# inductance_meter.net
KiCad netlist of a schematic drawn in EAGLE
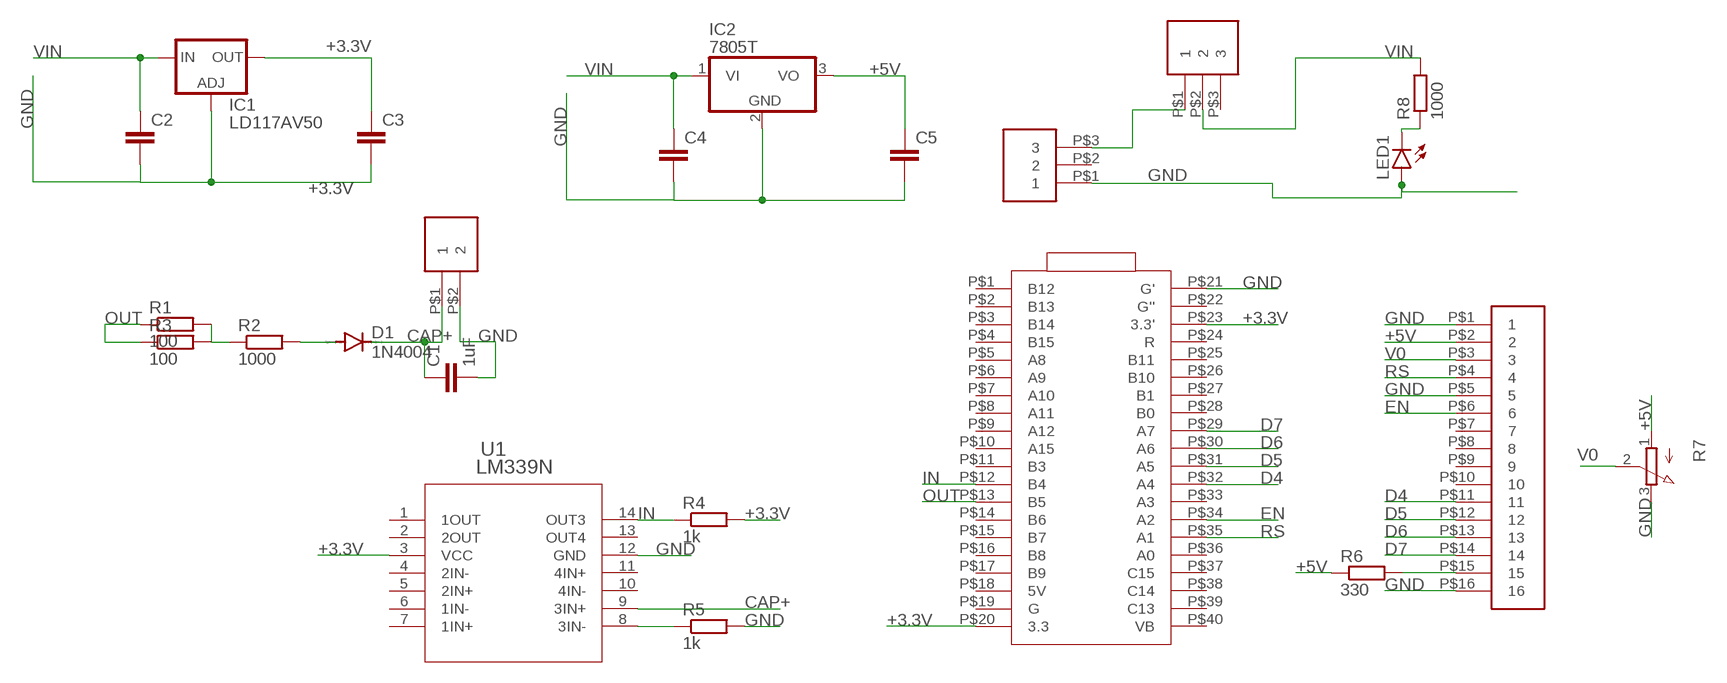
[diagram p0: schematic, sheet 1]

(export (version "E")
  (design (tool "Eeschema 10.0.6"))
  (components
    (comp (ref "C1")
      (value "1uF")
      (footprint "eagle-import:C050-075X075")
      (libsource (lib "eagle-import") (part "C-EU050-075X075"))
    )
    (comp (ref "C2")
      (value "C-EU025-030X050")
      (footprint "eagle-import:C025-030X050")
      (libsource (lib "eagle-import") (part "C-EU025-030X050"))
    )
    (comp (ref "C3")
      (value "C-EU025-030X050")
      (footprint "eagle-import:C025-030X050")
      (libsource (lib "eagle-import") (part "C-EU025-030X050"))
    )
    (comp (ref "C4")
      (value "C-EU025-030X050")
      (footprint "eagle-import:C025-030X050")
      (libsource (lib "eagle-import") (part "C-EU025-030X050"))
    )
    (comp (ref "C5")
      (value "C-EU025-030X050")
      (footprint "eagle-import:C025-030X050")
      (libsource (lib "eagle-import") (part "C-EU025-030X050"))
    )
    (comp (ref "D1")
      (value "1N4004")
      (footprint "eagle-import:DO41-10")
      (libsource (lib "eagle-import") (part "1N4004"))
    )
    (comp (ref "IC1")
      (value "LD117AV50")
      (footprint "eagle-import:TO220L1")
      (libsource (lib "eagle-import") (part "LD117A?V50"))
    )
    (comp (ref "IC2")
      (value "7805T")
      (footprint "eagle-import:TO220H")
      (libsource (lib "eagle-import") (part "78T05"))
    )
    (comp (ref "LED1")
      (value "TLLR4400")
      (footprint "eagle-import:LED3MM")
      (fields (field (name "MF") "VISHAY SEMICONDUCTOR"))
      (libsource (lib "eagle-import") (part "TLLR4400"))
    )
    (comp (ref "R1")
      (value "100")
      (footprint "eagle-import:P0817_22")
      (libsource (lib "eagle-import") (part "R-EU_0817/22"))
    )
    (comp (ref "R2")
      (value "1000")
      (footprint "eagle-import:P0817_22")
      (libsource (lib "eagle-import") (part "R-EU_0817/22"))
    )
    (comp (ref "R3")
      (value "100")
      (footprint "eagle-import:P0817_22")
      (libsource (lib "eagle-import") (part "R-EU_0817/22"))
    )
    (comp (ref "R4")
      (value "1k")
      (footprint "eagle-import:P0817_22")
      (libsource (lib "eagle-import") (part "R-EU_0817/22"))
    )
    (comp (ref "R5")
      (value "1k")
      (footprint "eagle-import:P0817_22")
      (libsource (lib "eagle-import") (part "R-EU_0817/22"))
    )
    (comp (ref "R6")
      (value "330")
      (footprint "eagle-import:0617_17")
      (libsource (lib "eagle-import") (part "R-EU_0617/17"))
    )
    (comp (ref "R7")
      (value "3RP/1610N")
      (footprint "eagle-import:3RP_1610N")
      (libsource (lib "eagle-import") (part "3RP/1610N"))
    )
    (comp (ref "R8")
      (value "1000")
      (footprint "eagle-import:P0817_22")
      (libsource (lib "eagle-import") (part "R-EU_0817/22"))
    )
    (comp (ref "U$2")
      (value "HEADER_16")
      (footprint "eagle-import:HEADER_16_FOOT")
      (libsource (lib "eagle-import") (part "HEADER_16"))
    )
    (comp (ref "U$3")
      (value "BLUE_PILL_EA")
      (footprint "eagle-import:BLUE_PILL_FOOT")
      (libsource (lib "eagle-import") (part "BLUE_PILL_EA"))
    )
    (comp (ref "U$5")
      (value "HEADER_2")
      (footprint "eagle-import:HEADER_2_FOOT")
      (libsource (lib "eagle-import") (part "HEADER_2"))
    )
    (comp (ref "U$7")
      (value "HEADER_3")
      (footprint "eagle-import:HEADER_3_FOOT")
      (libsource (lib "eagle-import") (part "HEADER_3"))
    )
    (comp (ref "U$9")
      (value "HEADER_3")
      (footprint "eagle-import:HEADER_3_FOOT")
      (libsource (lib "eagle-import") (part "HEADER_3"))
    )
    (comp (ref "U1")
      (value "LM339N")
      (footprint "eagle-import:PDIP14_6P60X19P69_ONS")
      (fields (field (name "COPYRIGHT") "Copyright (C) 2018 Accelerated Designs. All rights reserved"))
      (libsource (lib "eagle-import") (part "LM339N"))
    )
  )
  (nets
    (net (code "1") (name "/+3.3V") (class "Default")
      (node (ref "C3") (pin "1") (pinfunction "1_1") (pintype "passive"))
      (node (ref "IC1") (pin "2") (pinfunction "OUT_2") (pintype "passive"))
      (node (ref "R4") (pin "2") (pinfunction "2_2") (pintype "passive"))
      (node (ref "U$3") (pin "P$20") (pinfunction "3.3_P$20") (pintype "bidirectional"))
      (node (ref "U$3") (pin "P$23") (pinfunction "3.3'_P$23") (pintype "bidirectional"))
      (node (ref "U1") (pin "3") (pinfunction "VCC_3") (pintype "power_in"))
    )
    (net (code "2") (name "/+5V") (class "Default")
      (node (ref "C5") (pin "1") (pinfunction "1_1") (pintype "passive"))
      (node (ref "IC2") (pin "3") (pinfunction "VO_3") (pintype "passive"))
      (node (ref "R6") (pin "1") (pinfunction "1_1") (pintype "passive"))
      (node (ref "R7") (pin "1") (pinfunction "A_1") (pintype "passive"))
      (node (ref "U$2") (pin "P$2") (pinfunction "2_P$2") (pintype "bidirectional"))
    )
    (net (code "3") (name "/CAP+") (class "Default")
      (node (ref "C1") (pin "1") (pinfunction "1_1") (pintype "passive"))
      (node (ref "D1") (pin "C") (pinfunction "C_C") (pintype "passive"))
      (node (ref "U$5") (pin "P$1") (pinfunction "1_P$1") (pintype "bidirectional"))
      (node (ref "U1") (pin "9") (pinfunction "3IN+_9") (pintype "input"))
    )
    (net (code "4") (name "/D4") (class "Default")
      (node (ref "U$2") (pin "P$11") (pinfunction "11_P$11") (pintype "bidirectional"))
      (node (ref "U$3") (pin "P$32") (pinfunction "A4_P$32") (pintype "bidirectional"))
    )
    (net (code "5") (name "/D5") (class "Default")
      (node (ref "U$2") (pin "P$12") (pinfunction "12_P$12") (pintype "bidirectional"))
      (node (ref "U$3") (pin "P$31") (pinfunction "A5_P$31") (pintype "bidirectional"))
    )
    (net (code "6") (name "/D6") (class "Default")
      (node (ref "U$2") (pin "P$13") (pinfunction "13_P$13") (pintype "bidirectional"))
      (node (ref "U$3") (pin "P$30") (pinfunction "A6_P$30") (pintype "bidirectional"))
    )
    (net (code "7") (name "/D7") (class "Default")
      (node (ref "U$2") (pin "P$14") (pinfunction "14_P$14") (pintype "bidirectional"))
      (node (ref "U$3") (pin "P$29") (pinfunction "A7_P$29") (pintype "bidirectional"))
    )
    (net (code "8") (name "/EN") (class "Default")
      (node (ref "U$2") (pin "P$6") (pinfunction "6_P$6") (pintype "bidirectional"))
      (node (ref "U$3") (pin "P$34") (pinfunction "A2_P$34") (pintype "bidirectional"))
    )
    (net (code "9") (name "/GND") (class "Default")
      (node (ref "C1") (pin "2") (pinfunction "2_2") (pintype "passive"))
      (node (ref "C2") (pin "2") (pinfunction "2_2") (pintype "passive"))
      (node (ref "C3") (pin "2") (pinfunction "2_2") (pintype "passive"))
      (node (ref "C4") (pin "2") (pinfunction "2_2") (pintype "passive"))
      (node (ref "C5") (pin "2") (pinfunction "2_2") (pintype "passive"))
      (node (ref "IC1") (pin "1") (pinfunction "ADJ_1") (pintype "input"))
      (node (ref "IC2") (pin "2") (pinfunction "GND_2") (pintype "passive"))
      (node (ref "LED1") (pin "A") (pinfunction "A_A") (pintype "passive"))
      (node (ref "R5") (pin "2") (pinfunction "2_2") (pintype "passive"))
      (node (ref "R7") (pin "3") (pinfunction "E_3") (pintype "passive"))
      (node (ref "U$2") (pin "P$1") (pinfunction "1_P$1") (pintype "bidirectional"))
      (node (ref "U$2") (pin "P$16") (pinfunction "16_P$16") (pintype "bidirectional"))
      (node (ref "U$2") (pin "P$5") (pinfunction "5_P$5") (pintype "bidirectional"))
      (node (ref "U$3") (pin "P$21") (pinfunction "G'_P$21") (pintype "bidirectional"))
      (node (ref "U$5") (pin "P$2") (pinfunction "2_P$2") (pintype "bidirectional"))
      (node (ref "U$9") (pin "P$1") (pinfunction "1_P$1") (pintype "bidirectional"))
      (node (ref "U1") (pin "12") (pinfunction "GND_12") (pintype "power_in"))
    )
    (net (code "10") (name "/IN") (class "Default")
      (node (ref "R4") (pin "1") (pinfunction "1_1") (pintype "passive"))
      (node (ref "U$3") (pin "P$12") (pinfunction "B4_P$12") (pintype "bidirectional"))
      (node (ref "U1") (pin "14") (pinfunction "OUT3_14") (pintype "output"))
    )
    (net (code "11") (name "/OUT") (class "Default")
      (node (ref "R1") (pin "1") (pinfunction "1_1") (pintype "passive"))
      (node (ref "R3") (pin "1") (pinfunction "1_1") (pintype "passive"))
      (node (ref "U$3") (pin "P$13") (pinfunction "B5_P$13") (pintype "bidirectional"))
    )
    (net (code "12") (name "/RS") (class "Default")
      (node (ref "U$2") (pin "P$4") (pinfunction "4_P$4") (pintype "bidirectional"))
      (node (ref "U$3") (pin "P$35") (pinfunction "A1_P$35") (pintype "bidirectional"))
    )
    (net (code "13") (name "/V0") (class "Default")
      (node (ref "R7") (pin "2") (pinfunction "S_2") (pintype "passive"))
      (node (ref "U$2") (pin "P$3") (pinfunction "3_P$3") (pintype "bidirectional"))
    )
    (net (code "14") (name "/VIN") (class "Default")
      (node (ref "C2") (pin "1") (pinfunction "1_1") (pintype "passive"))
      (node (ref "C4") (pin "1") (pinfunction "1_1") (pintype "passive"))
      (node (ref "IC1") (pin "3") (pinfunction "IN_3") (pintype "input"))
      (node (ref "IC2") (pin "1") (pinfunction "VI_1") (pintype "input"))
      (node (ref "R8") (pin "2") (pinfunction "2_2") (pintype "passive"))
      (node (ref "U$7") (pin "P$2") (pinfunction "2_P$2") (pintype "bidirectional"))
    )
    (net (code "15") (name "Net-(D1-PadA)") (class "Default")
      (node (ref "D1") (pin "A") (pinfunction "A_A") (pintype "passive"))
      (node (ref "R2") (pin "2") (pinfunction "2_2") (pintype "passive"))
    )
    (net (code "16") (name "Net-(LED1-C)") (class "Default")
      (node (ref "LED1") (pin "K") (pinfunction "C_K") (pintype "passive"))
      (node (ref "R8") (pin "1") (pinfunction "1_1") (pintype "passive"))
    )
    (net (code "17") (name "Net-(R1-Pad2)") (class "Default")
      (node (ref "R1") (pin "2") (pinfunction "2_2") (pintype "passive"))
      (node (ref "R2") (pin "1") (pinfunction "1_1") (pintype "passive"))
      (node (ref "R3") (pin "2") (pinfunction "2_2") (pintype "passive"))
    )
    (net (code "18") (name "Net-(U$2-15)") (class "Default")
      (node (ref "R6") (pin "2") (pinfunction "2_2") (pintype "passive"))
      (node (ref "U$2") (pin "P$15") (pinfunction "15_P$15") (pintype "bidirectional"))
    )
    (net (code "19") (name "Net-(U$7-1)") (class "Default")
      (node (ref "U$7") (pin "P$1") (pinfunction "1_P$1") (pintype "bidirectional"))
      (node (ref "U$9") (pin "P$3") (pinfunction "3_P$3") (pintype "bidirectional"))
    )
    (net (code "20") (name "Net-(U1-3IN-)") (class "Default")
      (node (ref "R5") (pin "1") (pinfunction "1_1") (pintype "passive"))
      (node (ref "U1") (pin "8") (pinfunction "3IN-_8") (pintype "input"))
    )
    (net (code "21") (name "unconnected-(U$2-7-PadP$7)") (class "Default")
      (node (ref "U$2") (pin "P$7") (pinfunction "7_P$7") (pintype "bidirectional"))
    )
    (net (code "22") (name "unconnected-(U$2-8-PadP$8)") (class "Default")
      (node (ref "U$2") (pin "P$8") (pinfunction "8_P$8") (pintype "bidirectional"))
    )
    (net (code "23") (name "unconnected-(U$2-9-PadP$9)") (class "Default")
      (node (ref "U$2") (pin "P$9") (pinfunction "9_P$9") (pintype "bidirectional"))
    )
    (net (code "24") (name "unconnected-(U$2-10-PadP$10)") (class "Default")
      (node (ref "U$2") (pin "P$10") (pinfunction "10_P$10") (pintype "bidirectional"))
    )
    (net (code "25") (name "unconnected-(U$3-5V-PadP$18)") (class "Default")
      (node (ref "U$3") (pin "P$18") (pinfunction "5V_P$18") (pintype "bidirectional"))
    )
    (net (code "26") (name "unconnected-(U$3-A0-PadP$36)") (class "Default")
      (node (ref "U$3") (pin "P$36") (pinfunction "A0_P$36") (pintype "bidirectional"))
    )
    (net (code "27") (name "unconnected-(U$3-A3-PadP$33)") (class "Default")
      (node (ref "U$3") (pin "P$33") (pinfunction "A3_P$33") (pintype "bidirectional"))
    )
    (net (code "28") (name "unconnected-(U$3-A8-PadP$5)") (class "Default")
      (node (ref "U$3") (pin "P$5") (pinfunction "A8_P$5") (pintype "bidirectional"))
    )
    (net (code "29") (name "unconnected-(U$3-A9-PadP$6)") (class "Default")
      (node (ref "U$3") (pin "P$6") (pinfunction "A9_P$6") (pintype "bidirectional"))
    )
    (net (code "30") (name "unconnected-(U$3-A10-PadP$7)") (class "Default")
      (node (ref "U$3") (pin "P$7") (pinfunction "A10_P$7") (pintype "bidirectional"))
    )
    (net (code "31") (name "unconnected-(U$3-A11-PadP$8)") (class "Default")
      (node (ref "U$3") (pin "P$8") (pinfunction "A11_P$8") (pintype "bidirectional"))
    )
    (net (code "32") (name "unconnected-(U$3-A12-PadP$9)") (class "Default")
      (node (ref "U$3") (pin "P$9") (pinfunction "A12_P$9") (pintype "bidirectional"))
    )
    (net (code "33") (name "unconnected-(U$3-A15-PadP$10)") (class "Default")
      (node (ref "U$3") (pin "P$10") (pinfunction "A15_P$10") (pintype "bidirectional"))
    )
    (net (code "34") (name "unconnected-(U$3-B0-PadP$28)") (class "Default")
      (node (ref "U$3") (pin "P$28") (pinfunction "B0_P$28") (pintype "bidirectional"))
    )
    (net (code "35") (name "unconnected-(U$3-B1-PadP$27)") (class "Default")
      (node (ref "U$3") (pin "P$27") (pinfunction "B1_P$27") (pintype "bidirectional"))
    )
    (net (code "36") (name "unconnected-(U$3-B3-PadP$11)") (class "Default")
      (node (ref "U$3") (pin "P$11") (pinfunction "B3_P$11") (pintype "bidirectional"))
    )
    (net (code "37") (name "unconnected-(U$3-B6-PadP$14)") (class "Default")
      (node (ref "U$3") (pin "P$14") (pinfunction "B6_P$14") (pintype "bidirectional"))
    )
    (net (code "38") (name "unconnected-(U$3-B7-PadP$15)") (class "Default")
      (node (ref "U$3") (pin "P$15") (pinfunction "B7_P$15") (pintype "bidirectional"))
    )
    (net (code "39") (name "unconnected-(U$3-B8-PadP$16)") (class "Default")
      (node (ref "U$3") (pin "P$16") (pinfunction "B8_P$16") (pintype "bidirectional"))
    )
    (net (code "40") (name "unconnected-(U$3-B9-PadP$17)") (class "Default")
      (node (ref "U$3") (pin "P$17") (pinfunction "B9_P$17") (pintype "bidirectional"))
    )
    (net (code "41") (name "unconnected-(U$3-B10-PadP$26)") (class "Default")
      (node (ref "U$3") (pin "P$26") (pinfunction "B10_P$26") (pintype "bidirectional"))
    )
    (net (code "42") (name "unconnected-(U$3-B11-PadP$25)") (class "Default")
      (node (ref "U$3") (pin "P$25") (pinfunction "B11_P$25") (pintype "bidirectional"))
    )
    (net (code "43") (name "unconnected-(U$3-B12-PadP$1)") (class "Default")
      (node (ref "U$3") (pin "P$1") (pinfunction "B12_P$1") (pintype "bidirectional"))
    )
    (net (code "44") (name "unconnected-(U$3-B13-PadP$2)") (class "Default")
      (node (ref "U$3") (pin "P$2") (pinfunction "B13_P$2") (pintype "bidirectional"))
    )
    (net (code "45") (name "unconnected-(U$3-B14-PadP$3)") (class "Default")
      (node (ref "U$3") (pin "P$3") (pinfunction "B14_P$3") (pintype "bidirectional"))
    )
    (net (code "46") (name "unconnected-(U$3-B15-PadP$4)") (class "Default")
      (node (ref "U$3") (pin "P$4") (pinfunction "B15_P$4") (pintype "bidirectional"))
    )
    (net (code "47") (name "unconnected-(U$3-C13-PadP$39)") (class "Default")
      (node (ref "U$3") (pin "P$39") (pinfunction "C13_P$39") (pintype "bidirectional"))
    )
    (net (code "48") (name "unconnected-(U$3-C14-PadP$38)") (class "Default")
      (node (ref "U$3") (pin "P$38") (pinfunction "C14_P$38") (pintype "bidirectional"))
    )
    (net (code "49") (name "unconnected-(U$3-C15-PadP$37)") (class "Default")
      (node (ref "U$3") (pin "P$37") (pinfunction "C15_P$37") (pintype "bidirectional"))
    )
    (net (code "50") (name "unconnected-(U$3-G''-PadP$22)") (class "Default")
      (node (ref "U$3") (pin "P$22") (pinfunction "G''_P$22") (pintype "bidirectional"))
    )
    (net (code "51") (name "unconnected-(U$3-G-PadP$19)") (class "Default")
      (node (ref "U$3") (pin "P$19") (pinfunction "G_P$19") (pintype "bidirectional"))
    )
    (net (code "52") (name "unconnected-(U$3-R-PadP$24)") (class "Default")
      (node (ref "U$3") (pin "P$24") (pinfunction "R_P$24") (pintype "bidirectional"))
    )
    (net (code "53") (name "unconnected-(U$3-VB-PadP$40)") (class "Default")
      (node (ref "U$3") (pin "P$40") (pinfunction "VB_P$40") (pintype "bidirectional"))
    )
    (net (code "54") (name "unconnected-(U$7-3-PadP$3)") (class "Default")
      (node (ref "U$7") (pin "P$3") (pinfunction "3_P$3") (pintype "bidirectional"))
    )
    (net (code "55") (name "unconnected-(U$9-2-PadP$2)") (class "Default")
      (node (ref "U$9") (pin "P$2") (pinfunction "2_P$2") (pintype "bidirectional"))
    )
    (net (code "56") (name "unconnected-(U1-1IN+-Pad7)") (class "Default")
      (node (ref "U1") (pin "7") (pinfunction "1IN+_7") (pintype "input"))
    )
    (net (code "57") (name "unconnected-(U1-1IN--Pad6)") (class "Default")
      (node (ref "U1") (pin "6") (pinfunction "1IN-_6") (pintype "input"))
    )
    (net (code "58") (name "unconnected-(U1-1OUT-Pad1)") (class "Default")
      (node (ref "U1") (pin "1") (pinfunction "1OUT_1") (pintype "output"))
    )
    (net (code "59") (name "unconnected-(U1-2IN+-Pad5)") (class "Default")
      (node (ref "U1") (pin "5") (pinfunction "2IN+_5") (pintype "input"))
    )
    (net (code "60") (name "unconnected-(U1-2IN--Pad4)") (class "Default")
      (node (ref "U1") (pin "4") (pinfunction "2IN-_4") (pintype "input"))
    )
    (net (code "61") (name "unconnected-(U1-2OUT-Pad2)") (class "Default")
      (node (ref "U1") (pin "2") (pinfunction "2OUT_2") (pintype "output"))
    )
    (net (code "62") (name "unconnected-(U1-4IN+-Pad11)") (class "Default")
      (node (ref "U1") (pin "11") (pinfunction "4IN+_11") (pintype "input"))
    )
    (net (code "63") (name "unconnected-(U1-4IN--Pad10)") (class "Default")
      (node (ref "U1") (pin "10") (pinfunction "4IN-_10") (pintype "input"))
    )
    (net (code "64") (name "unconnected-(U1-OUT4-Pad13)") (class "Default")
      (node (ref "U1") (pin "13") (pinfunction "OUT4_13") (pintype "output"))
    )
  )
)
